# ProProject_ESP8266_healthy_2025-04-15.net
KiCad netlist of a schematic drawn in EasyEDA Pro
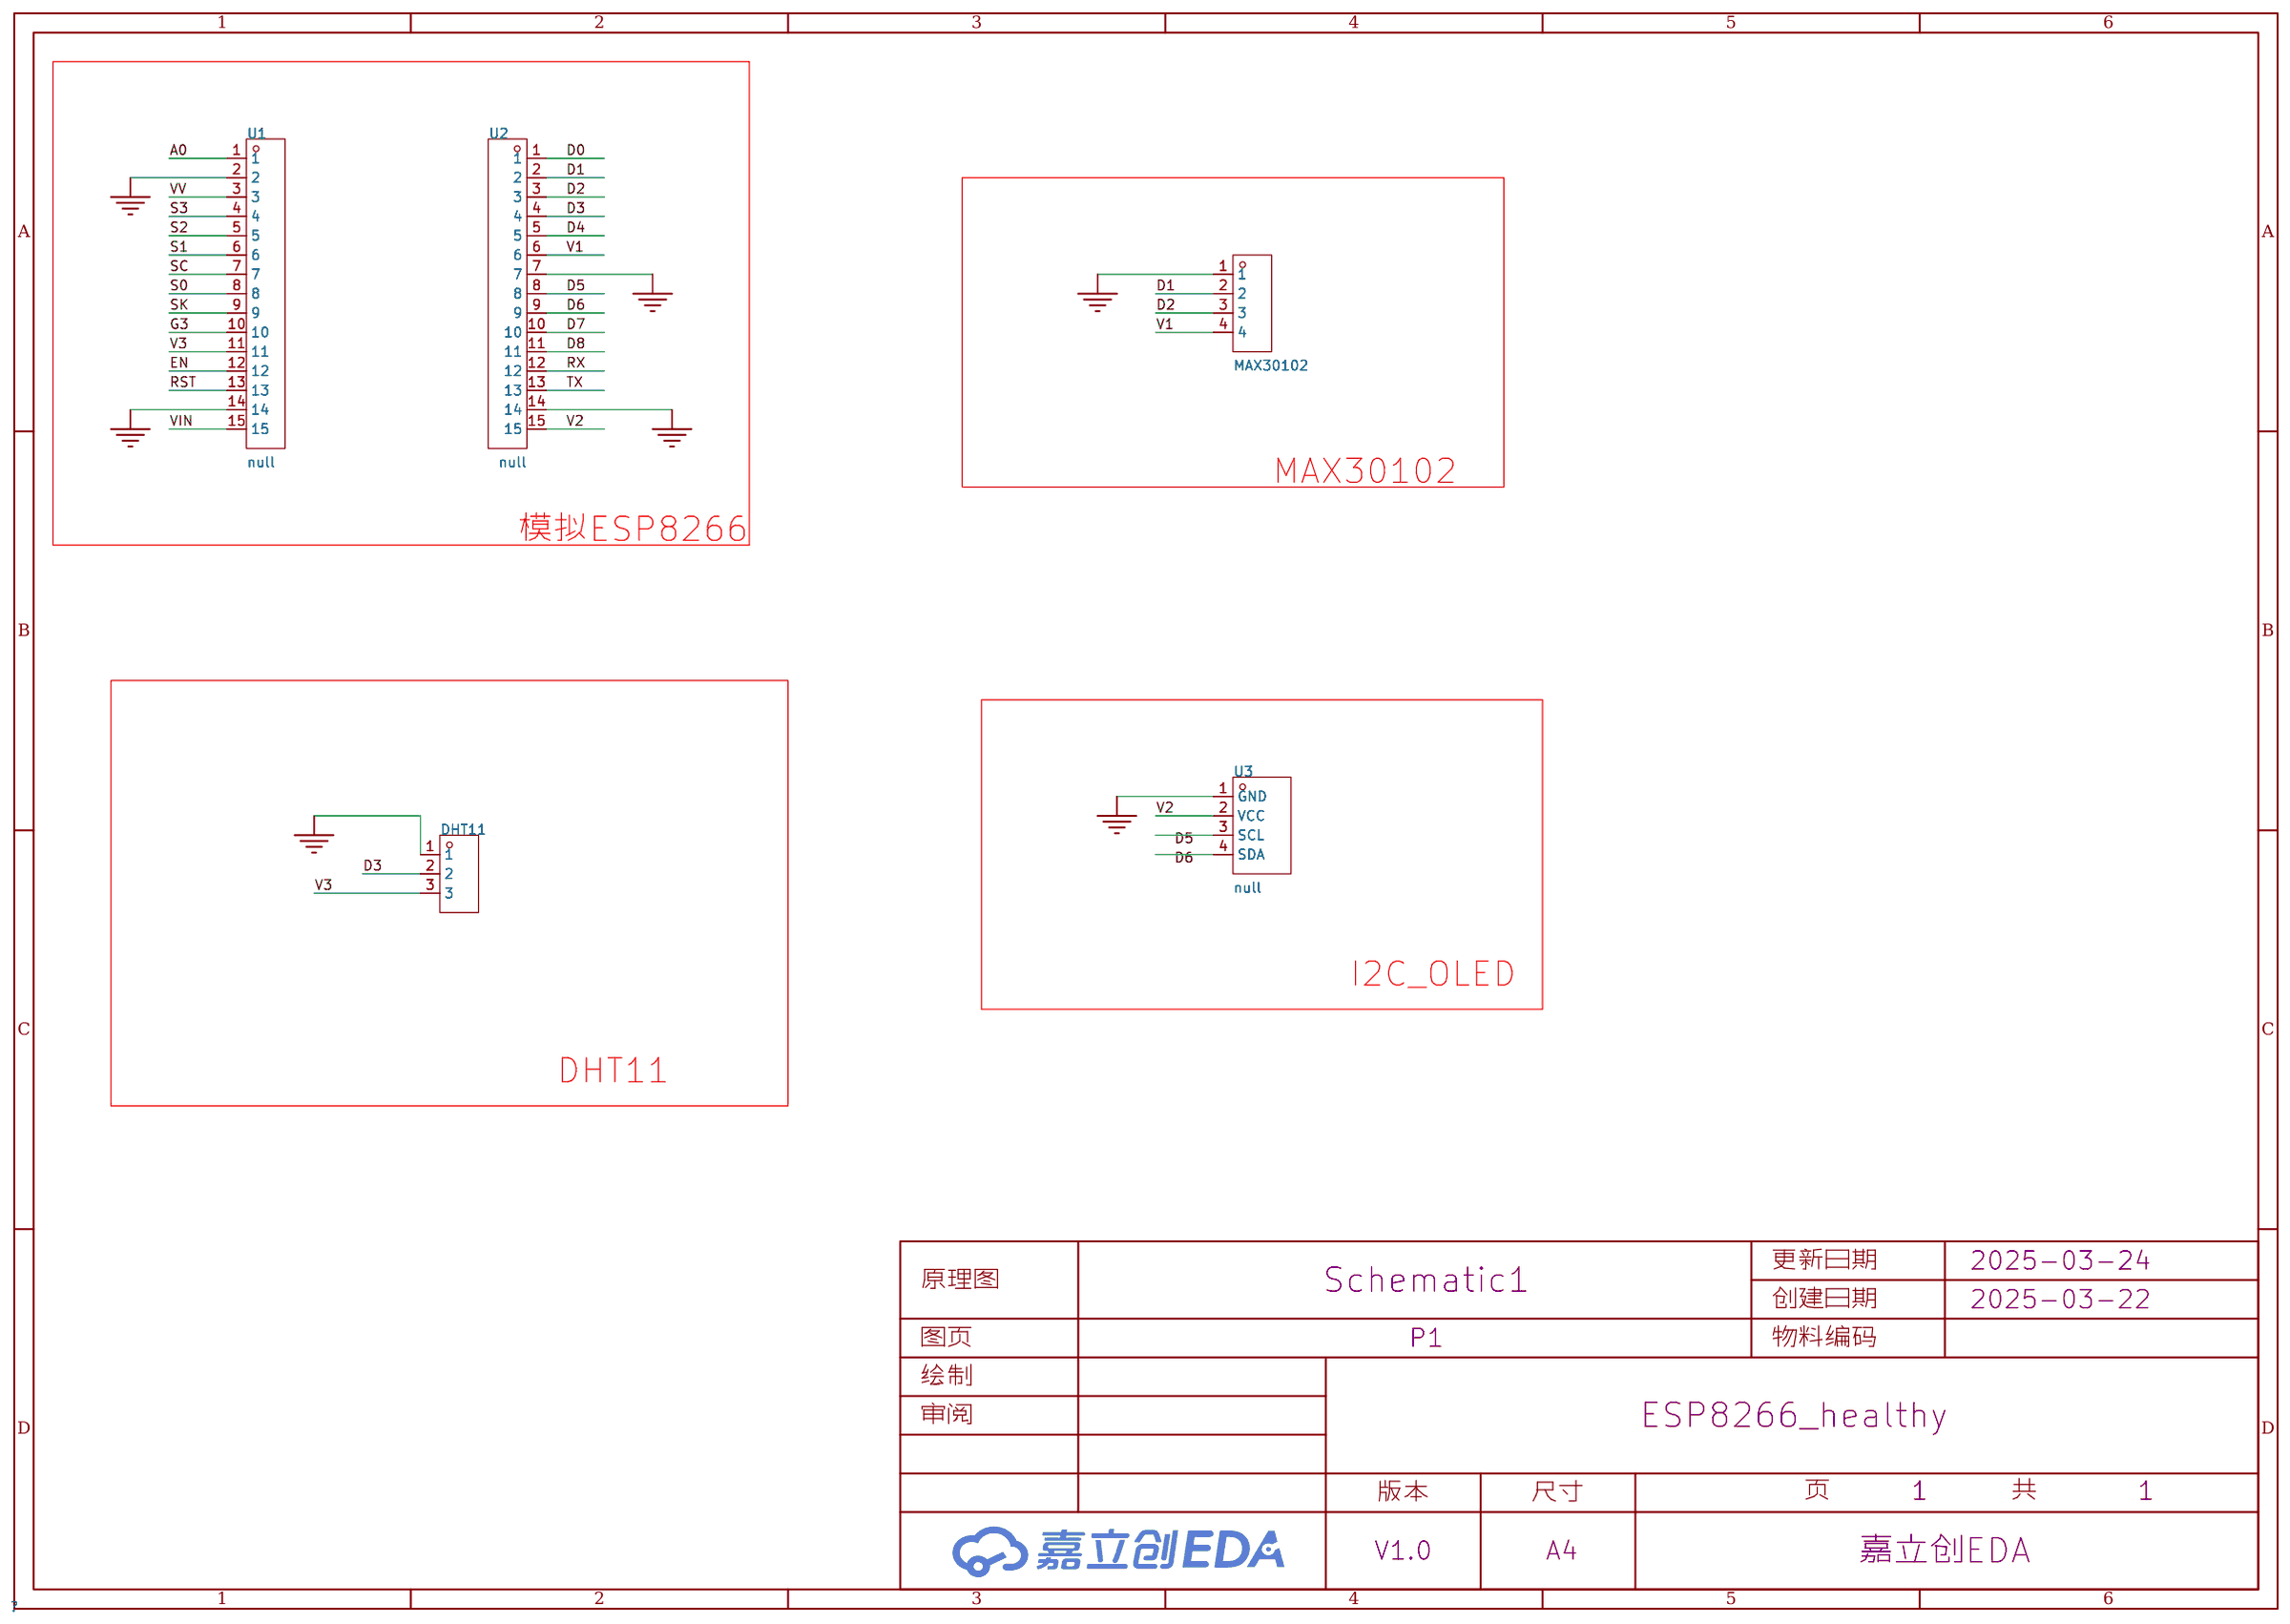
[diagram p0: schematic sheet]

(export (version "E")
  (design (tool "Eeschema 10.0.6"))
  (components
    (comp (ref "DHT11")
      (value "VCC")
      (footprint "easyedapro:HDR-TH_3P-P2.54-V-F")
      (libsource (lib "easyedapro") (part "PM254V-11-03-H85"))
    )
    (comp (ref "MAX30102")
      (value "~")
      (footprint "easyedapro:HDR-TH_4P-P2.54-V-F")
      (libsource (lib "easyedapro") (part "2.54-1*4P母"))
    )
    (comp (ref "U1")
      (value "null")
      (footprint "easyedapro:HDR-TH_15P-P2.54-V-F")
      (fields
        (field (name "Manufacturer Part") "KH-2.54FH-1X15P-H8.5")
        (field (name "Manufacturer") "kinghelm(金航标)")
      )
      (libsource (lib "easyedapro") (part "KH-2.54FH-1X15P-H8.5"))
    )
    (comp (ref "U2")
      (value "null")
      (footprint "easyedapro:HDR-TH_15P-P2.54-V-F")
      (fields
        (field (name "Manufacturer Part") "ESP8266 CH340 串口WIFI模块")
        (field (name "Manufacturer") "kinghelm(金航标)")
      )
      (libsource (lib "easyedapro") (part "KH-2.54FH-1X15P-H8.5"))
    )
    (comp (ref "U3")
      (value "null")
      (footprint "easyedapro:OLED-TH_L27.8-W27.2-P2.54_C9900033791")
      (description "主控芯片:SSD1315;接口类型:I2C;尺寸(inch):0.96;像素分辨率:128x64;")
      (fields (field (name "Manufacturer Part") "OLED") (field (name "Manufacturer") "HS(汉昇)"))
      (libsource (lib "easyedapro") (part "HS96L03W2C03"))
    )
  )
  (nets
    (net (code "1") (name "/A0") (class "Default")
      (node (ref "U1") (pin "1") (pinfunction "1_1") (pintype "unspecified"))
    )
    (net (code "2") (name "/D0") (class "Default")
      (node (ref "U2") (pin "1") (pinfunction "1_1") (pintype "unspecified"))
    )
    (net (code "3") (name "/D1") (class "Default")
      (node (ref "MAX30102") (pin "2") (pinfunction "2_2") (pintype "unspecified"))
      (node (ref "U2") (pin "2") (pinfunction "2_2") (pintype "unspecified"))
    )
    (net (code "4") (name "/D2") (class "Default")
      (node (ref "MAX30102") (pin "3") (pinfunction "3_3") (pintype "unspecified"))
      (node (ref "U2") (pin "3") (pinfunction "3_3") (pintype "unspecified"))
    )
    (net (code "5") (name "/D3") (class "Default")
      (node (ref "DHT11") (pin "2") (pinfunction "2_2") (pintype "unspecified"))
      (node (ref "U2") (pin "4") (pinfunction "4_4") (pintype "unspecified"))
    )
    (net (code "6") (name "/D4") (class "Default")
      (node (ref "U2") (pin "5") (pinfunction "5_5") (pintype "unspecified"))
    )
    (net (code "7") (name "/D5") (class "Default")
      (node (ref "U2") (pin "8") (pinfunction "8_8") (pintype "unspecified"))
      (node (ref "U3") (pin "3") (pinfunction "SCL_3") (pintype "unspecified"))
    )
    (net (code "8") (name "/D6") (class "Default")
      (node (ref "U2") (pin "9") (pinfunction "9_9") (pintype "unspecified"))
      (node (ref "U3") (pin "4") (pinfunction "SDA_4") (pintype "unspecified"))
    )
    (net (code "9") (name "/D7") (class "Default")
      (node (ref "U2") (pin "10") (pinfunction "10_10") (pintype "unspecified"))
    )
    (net (code "10") (name "/D8") (class "Default")
      (node (ref "U2") (pin "11") (pinfunction "11_11") (pintype "unspecified"))
    )
    (net (code "11") (name "/EN") (class "Default")
      (node (ref "U1") (pin "12") (pinfunction "12_12") (pintype "unspecified"))
    )
    (net (code "12") (name "/G3") (class "Default")
      (node (ref "U1") (pin "10") (pinfunction "10_10") (pintype "unspecified"))
    )
    (net (code "13") (name "/RST") (class "Default")
      (node (ref "U1") (pin "13") (pinfunction "13_13") (pintype "unspecified"))
    )
    (net (code "14") (name "/RX") (class "Default")
      (node (ref "U2") (pin "12") (pinfunction "12_12") (pintype "unspecified"))
    )
    (net (code "15") (name "/S0") (class "Default")
      (node (ref "U1") (pin "8") (pinfunction "8_8") (pintype "unspecified"))
    )
    (net (code "16") (name "/S1") (class "Default")
      (node (ref "U1") (pin "6") (pinfunction "6_6") (pintype "unspecified"))
    )
    (net (code "17") (name "/S2") (class "Default")
      (node (ref "U1") (pin "5") (pinfunction "5_5") (pintype "unspecified"))
    )
    (net (code "18") (name "/S3") (class "Default")
      (node (ref "U1") (pin "4") (pinfunction "4_4") (pintype "unspecified"))
    )
    (net (code "19") (name "/SC") (class "Default")
      (node (ref "U1") (pin "7") (pinfunction "7_7") (pintype "unspecified"))
    )
    (net (code "20") (name "/SK") (class "Default")
      (node (ref "U1") (pin "9") (pinfunction "9_9") (pintype "unspecified"))
    )
    (net (code "21") (name "/TX") (class "Default")
      (node (ref "U2") (pin "13") (pinfunction "13_13") (pintype "unspecified"))
    )
    (net (code "22") (name "/V1") (class "Default")
      (node (ref "MAX30102") (pin "4") (pinfunction "4_4") (pintype "unspecified"))
      (node (ref "U2") (pin "6") (pinfunction "6_6") (pintype "unspecified"))
    )
    (net (code "23") (name "/V2") (class "Default")
      (node (ref "U2") (pin "15") (pinfunction "15_15") (pintype "unspecified"))
      (node (ref "U3") (pin "2") (pinfunction "VCC_2") (pintype "unspecified"))
    )
    (net (code "24") (name "/V3") (class "Default")
      (node (ref "DHT11") (pin "3") (pinfunction "3_3") (pintype "unspecified"))
      (node (ref "U1") (pin "11") (pinfunction "11_11") (pintype "unspecified"))
    )
    (net (code "25") (name "/VIN") (class "Default")
      (node (ref "U1") (pin "15") (pinfunction "15_15") (pintype "unspecified"))
    )
    (net (code "26") (name "/VV") (class "Default")
      (node (ref "U1") (pin "3") (pinfunction "3_3") (pintype "unspecified"))
    )
    (net (code "27") (name "GND") (class "Default")
      (node (ref "DHT11") (pin "1") (pinfunction "1_1") (pintype "unspecified"))
      (node (ref "MAX30102") (pin "1") (pinfunction "1_1") (pintype "unspecified"))
      (node (ref "U1") (pin "14") (pinfunction "14_14") (pintype "unspecified"))
      (node (ref "U1") (pin "2") (pinfunction "2_2") (pintype "unspecified"))
      (node (ref "U2") (pin "14") (pinfunction "14_14") (pintype "unspecified"))
      (node (ref "U2") (pin "7") (pinfunction "7_7") (pintype "unspecified"))
      (node (ref "U3") (pin "1") (pinfunction "GND_1") (pintype "unspecified"))
    )
  )
)
